# LineSensor.net
KiCad netlist of a schematic drawn in EasyEDA
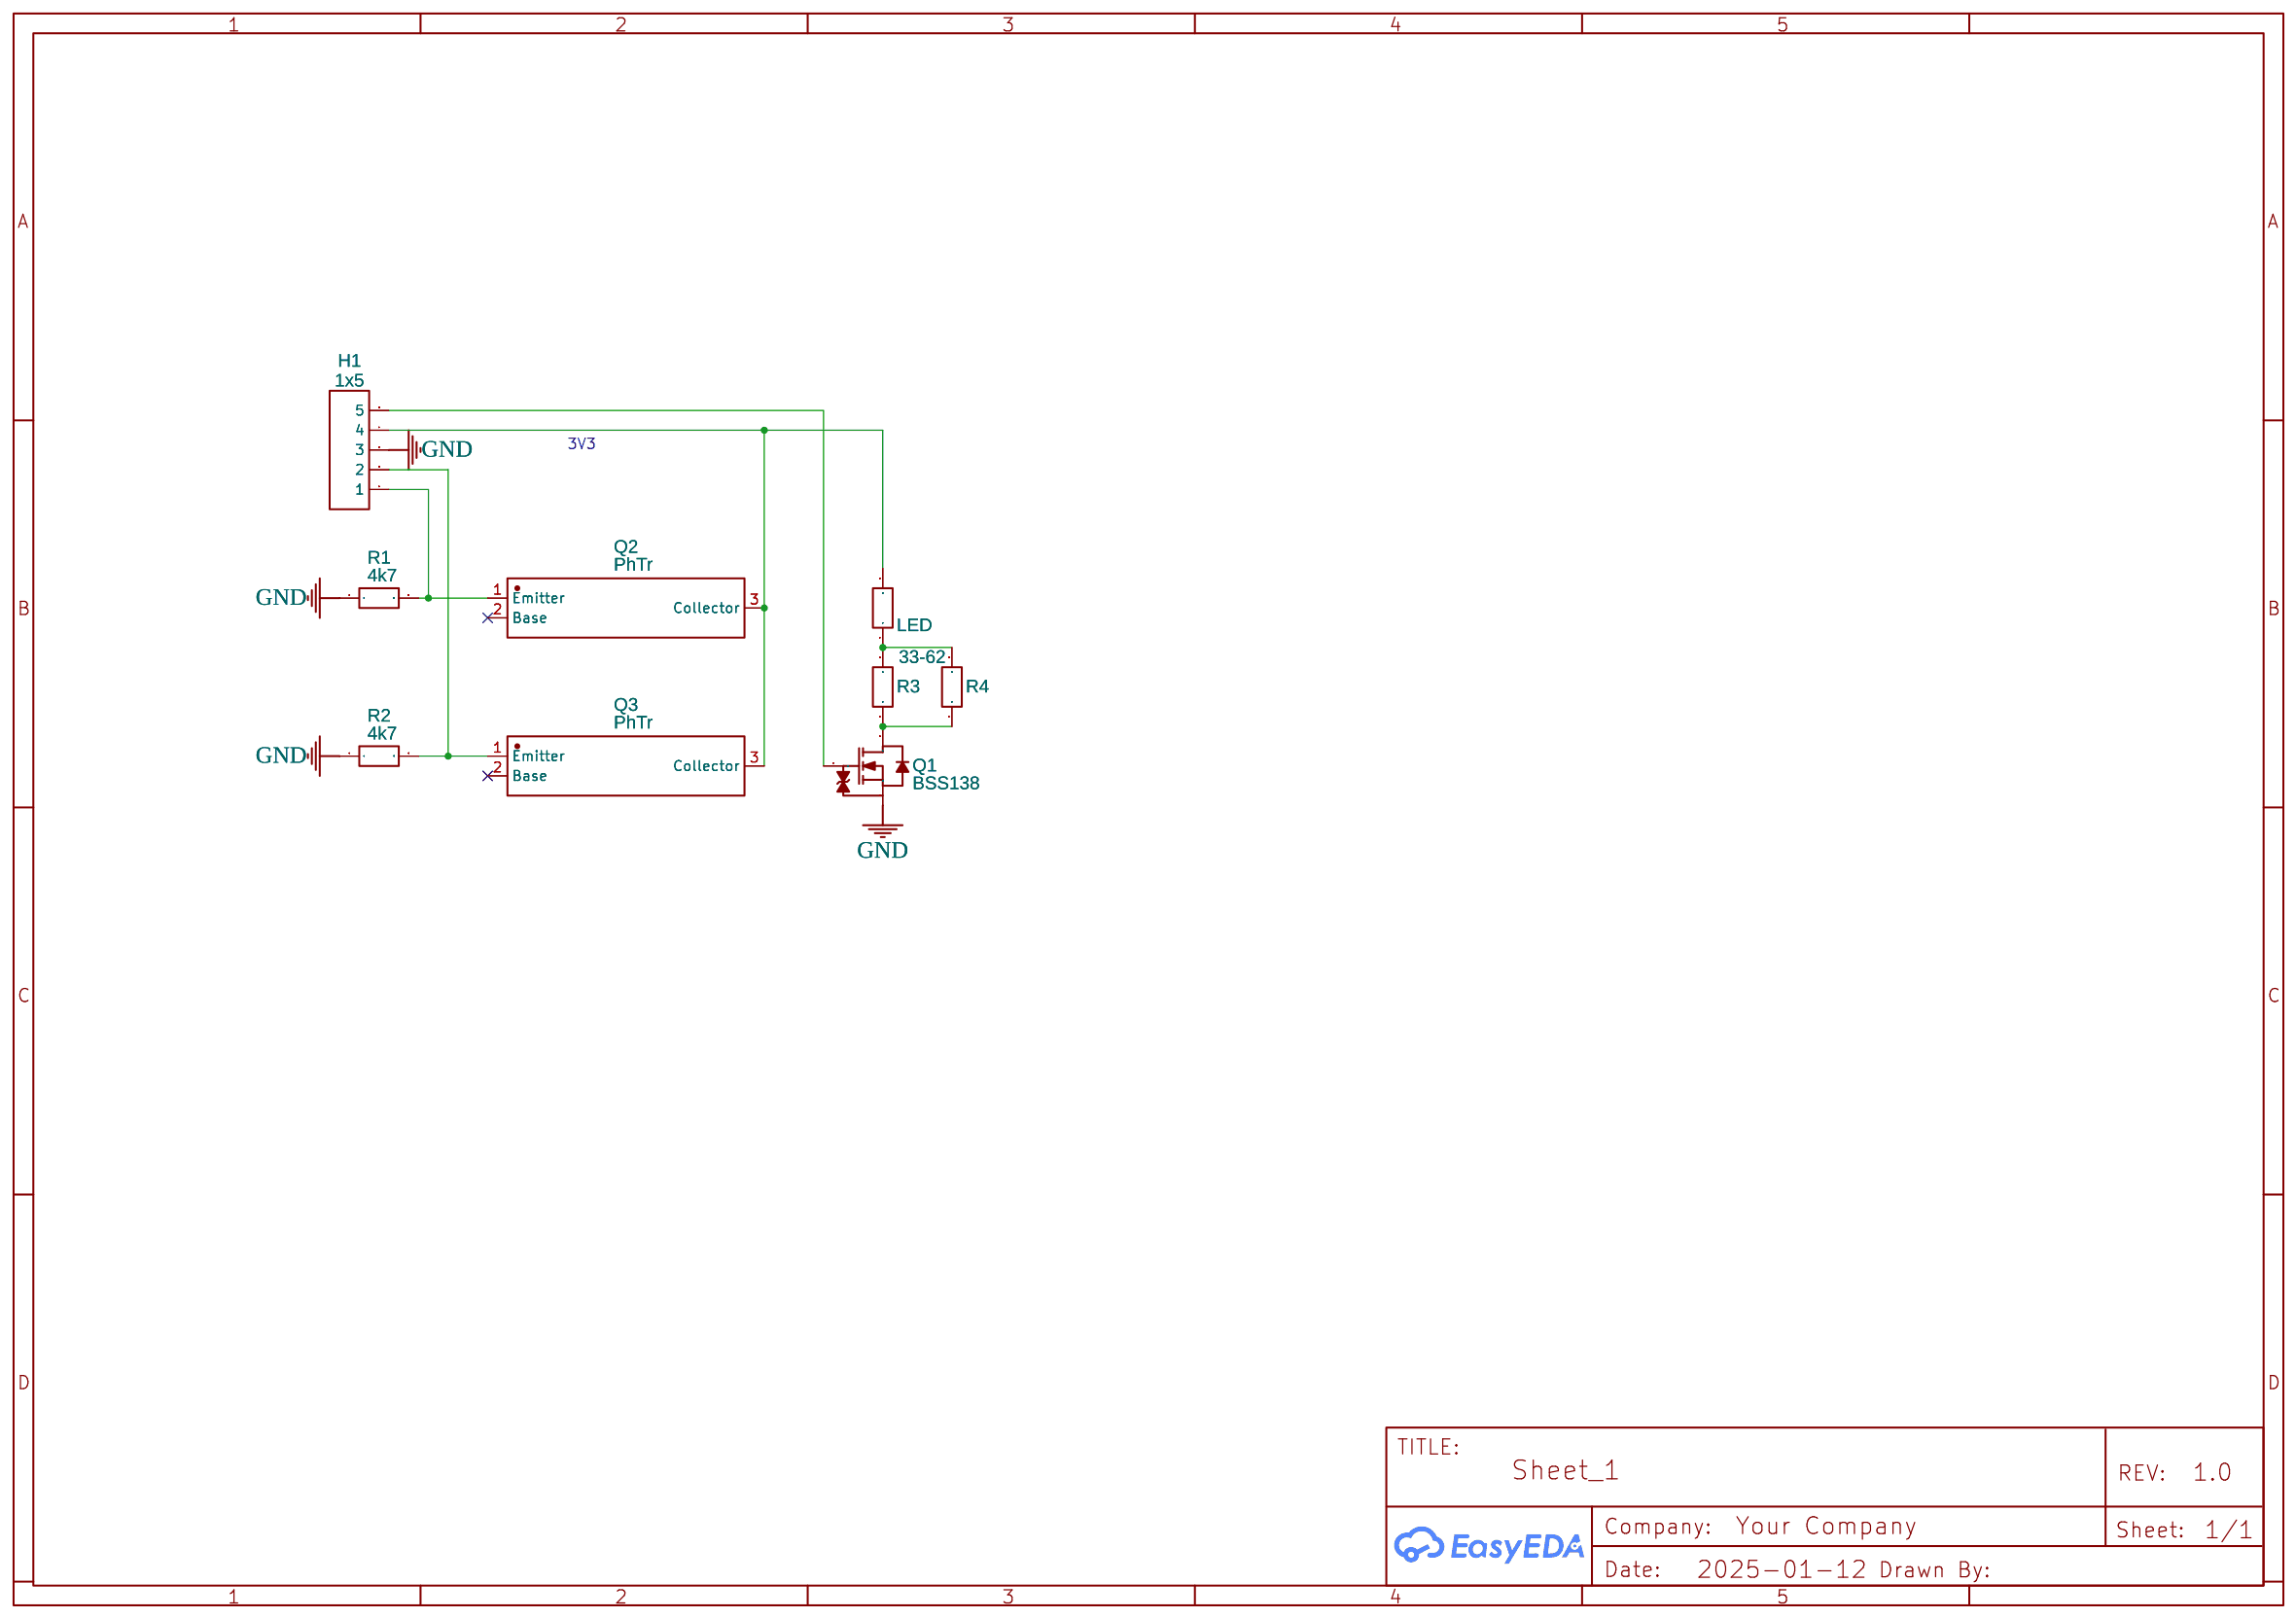
[diagram p0: schematic sheet]

(export (version "E")
  (design (tool "Eeschema 10.0.6"))
  (components
    (comp (ref "H1") (value "1x5") (libsource (lib "") (part "HDR-F-2.54_1x5")))
    (comp (ref "Q1")
      (value "BSS138")
      (fields (field (name "Manufacturer Part") "BSS138BK") (field (name "Manufacturer") "ElecSuper(静芯微)"))
      (libsource (lib "") (part "BSS138BK"))
    )
    (comp (ref "Q2")
      (value "PhTr")
      (fields (field (name "Manufacturer Part") "BC107 PBFREE") (field (name "Manufacturer") "Central(中环)"))
      (libsource (lib "") (part "BC107 PBFREE"))
    )
    (comp (ref "Q3")
      (value "PhTr")
      (fields (field (name "Manufacturer Part") "BC107 PBFREE") (field (name "Manufacturer") "Central(中环)"))
      (libsource (lib "") (part "BC107 PBFREE"))
    )
    (comp (ref "R1") (value "4k7") (libsource (lib "") (part "R_1206_EU")))
    (comp (ref "R2") (value "4k7") (libsource (lib "") (part "R_1206_EU")))
    (comp (ref "R3") (value "33") (libsource (lib "") (part "R_1206_EU_1")))
    (comp (ref "R4") (value "33-62") (libsource (lib "") (part "R_AXIAL-0.3_EU")))
    (comp (ref "R5") (value "LED") (libsource (lib "") (part "R_AXIAL-0.6_EU")))
  )
  (nets
    (net (code "1") (name "GND") (class "Default")
      (node (ref "H1") (pin "3") (pinfunction "3_3") (pintype "unspecified"))
      (node (ref "Q1") (pin "2") (pinfunction "S_2") (pintype "unspecified"))
      (node (ref "R1") (pin "1") (pinfunction "1_1") (pintype "unspecified"))
      (node (ref "R2") (pin "1") (pinfunction "1_1") (pintype "unspecified"))
    )
    (net (code "2") (name "Net-(Q1-D)") (class "Default")
      (node (ref "Q1") (pin "3") (pinfunction "D_3") (pintype "unspecified"))
      (node (ref "R3") (pin "1") (pinfunction "1_1") (pintype "unspecified"))
      (node (ref "R4") (pin "1") (pinfunction "1_1") (pintype "unspecified"))
    )
    (net (code "3") (name "Net-(Q1-G)") (class "Default")
      (node (ref "H1") (pin "5") (pinfunction "5_5") (pintype "unspecified"))
      (node (ref "Q1") (pin "1") (pinfunction "G_1") (pintype "unspecified"))
    )
    (net (code "4") (name "Net-(Q2-Collector)") (class "Default")
      (node (ref "H1") (pin "4") (pinfunction "4_4") (pintype "unspecified"))
      (node (ref "Q2") (pin "3") (pinfunction "Collector_3") (pintype "unspecified"))
      (node (ref "Q3") (pin "3") (pinfunction "Collector_3") (pintype "unspecified"))
      (node (ref "R5") (pin "2") (pinfunction "2_2") (pintype "unspecified"))
    )
    (net (code "5") (name "Net-(Q2-Emitter)") (class "Default")
      (node (ref "H1") (pin "1") (pinfunction "1_1") (pintype "unspecified"))
      (node (ref "Q2") (pin "1") (pinfunction "Emitter_1") (pintype "unspecified"))
      (node (ref "R1") (pin "2") (pinfunction "2_2") (pintype "unspecified"))
    )
    (net (code "6") (name "Net-(Q3-Emitter)") (class "Default")
      (node (ref "H1") (pin "2") (pinfunction "2_2") (pintype "unspecified"))
      (node (ref "Q3") (pin "1") (pinfunction "Emitter_1") (pintype "unspecified"))
      (node (ref "R2") (pin "2") (pinfunction "2_2") (pintype "unspecified"))
    )
    (net (code "7") (name "Net-(R3-Pad2)") (class "Default")
      (node (ref "R3") (pin "2") (pinfunction "2_2") (pintype "unspecified"))
      (node (ref "R4") (pin "2") (pinfunction "2_2") (pintype "unspecified"))
      (node (ref "R5") (pin "1") (pinfunction "1_1") (pintype "unspecified"))
    )
    (net (code "8") (name "unconnected-(Q2-Base-Pad2)") (class "Default")
      (node (ref "Q2") (pin "2") (pinfunction "Base_2") (pintype "unspecified+no_connect"))
    )
    (net (code "9") (name "unconnected-(Q3-Base-Pad2)") (class "Default")
      (node (ref "Q3") (pin "2") (pinfunction "Base_2") (pintype "unspecified+no_connect"))
    )
  )
)
